# Optical_indication.net
KiCad netlist of a schematic drawn in Altium Designer
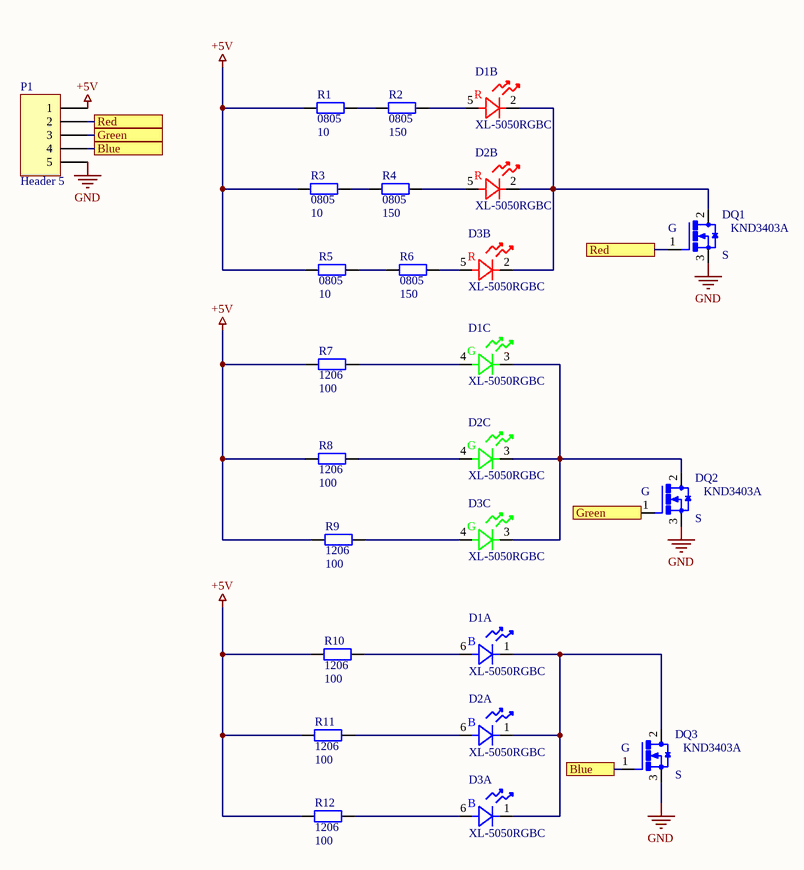
[diagram p0: Optical indication.SchDoc]

(export (version "E")
  (design (tool "Eeschema 10.0.6"))
  (components
    (comp (ref "D1")
      (value "XL-5050RGBC")
      (footprint "XL-5050RGBC")
      (libsource (lib "XL-5050RGBC") (part "XL-5050RGBC"))
    )
    (comp (ref "D2")
      (value "XL-5050RGBC")
      (footprint "XL-5050RGBC")
      (libsource (lib "XL-5050RGBC") (part "XL-5050RGBC"))
    )
    (comp (ref "D3")
      (value "XL-5050RGBC")
      (footprint "XL-5050RGBC")
      (libsource (lib "XL-5050RGBC") (part "XL-5050RGBC"))
    )
    (comp (ref "P1")
      (value "Header 5")
      (footprint "HDR1X5")
      (description "Header, 5-Pin")
      (fields (field (name "PUBLISHER") "Altium Limited"))
      (libsource (lib "Miscellaneous Connectors") (part "Header 5"))
    )
    (comp (ref "Q1")
      (value "KND3403A")
      (footprint "TO252")
      (description "N-CHANNEL MOSFET")
      (libsource (lib "KND3403A") (part "KND3403A"))
    )
    (comp (ref "Q2")
      (value "KND3403A")
      (footprint "TO252")
      (description "N-CHANNEL MOSFET")
      (libsource (lib "KND3403A") (part "KND3403A"))
    )
    (comp (ref "Q3")
      (value "KND3403A")
      (footprint "TO252")
      (description "N-CHANNEL MOSFET")
      (libsource (lib "KND3403A") (part "KND3403A"))
    )
    (comp (ref "R1")
      (value "0805")
      (footprint "AXIAL-0.4")
      (description "Resistor")
      (fields (field (name "ALTIUM_VALUE") "10") (field (name "PUBLISHER") "Altium Limited"))
      (libsource (lib "Miscellaneous Devices") (part "Res2"))
    )
    (comp (ref "R2")
      (value "0805")
      (footprint "AXIAL-0.4")
      (description "Resistor")
      (fields (field (name "ALTIUM_VALUE") "150") (field (name "PUBLISHER") "Altium Limited"))
      (libsource (lib "") (part "Res2_1"))
    )
    (comp (ref "R3")
      (value "0805")
      (footprint "AXIAL-0.4")
      (description "Resistor")
      (fields (field (name "ALTIUM_VALUE") "10") (field (name "PUBLISHER") "Altium Limited"))
      (libsource (lib "Miscellaneous Devices") (part "Res2"))
    )
    (comp (ref "R4")
      (value "0805")
      (footprint "AXIAL-0.4")
      (description "Resistor")
      (fields (field (name "ALTIUM_VALUE") "150") (field (name "PUBLISHER") "Altium Limited"))
      (libsource (lib "") (part "Res2_1"))
    )
    (comp (ref "R5")
      (value "0805")
      (footprint "AXIAL-0.4")
      (description "Resistor")
      (fields (field (name "ALTIUM_VALUE") "10") (field (name "PUBLISHER") "Altium Limited"))
      (libsource (lib "Miscellaneous Devices") (part "Res2"))
    )
    (comp (ref "R6")
      (value "0805")
      (footprint "AXIAL-0.4")
      (description "Resistor")
      (fields (field (name "ALTIUM_VALUE") "150") (field (name "PUBLISHER") "Altium Limited"))
      (libsource (lib "Miscellaneous Devices") (part "Res2"))
    )
    (comp (ref "R7")
      (value "1206")
      (footprint "AXIAL-0.4")
      (description "Resistor")
      (fields (field (name "ALTIUM_VALUE") "100") (field (name "PUBLISHER") "Altium Limited"))
      (libsource (lib "Miscellaneous Devices") (part "Res2"))
    )
    (comp (ref "R8")
      (value "1206")
      (footprint "AXIAL-0.4")
      (description "Resistor")
      (fields (field (name "ALTIUM_VALUE") "100") (field (name "PUBLISHER") "Altium Limited"))
      (libsource (lib "Miscellaneous Devices") (part "Res2"))
    )
    (comp (ref "R9")
      (value "1206")
      (footprint "AXIAL-0.4")
      (description "Resistor")
      (fields (field (name "ALTIUM_VALUE") "100") (field (name "PUBLISHER") "Altium Limited"))
      (libsource (lib "Miscellaneous Devices") (part "Res2"))
    )
    (comp (ref "R10")
      (value "1206")
      (footprint "AXIAL-0.4")
      (description "Resistor")
      (fields (field (name "ALTIUM_VALUE") "100") (field (name "PUBLISHER") "Altium Limited"))
      (libsource (lib "Miscellaneous Devices") (part "Res2"))
    )
    (comp (ref "R11")
      (value "1206")
      (footprint "AXIAL-0.4")
      (description "Resistor")
      (fields (field (name "ALTIUM_VALUE") "100") (field (name "PUBLISHER") "Altium Limited"))
      (libsource (lib "Miscellaneous Devices") (part "Res2"))
    )
    (comp (ref "R12")
      (value "1206")
      (footprint "AXIAL-0.4")
      (description "Resistor")
      (fields (field (name "ALTIUM_VALUE") "100") (field (name "PUBLISHER") "Altium Limited"))
      (libsource (lib "Miscellaneous Devices") (part "Res2"))
    )
  )
  (nets
    (net (code "1") (name "+5V") (class "Default")
      (node (ref "P1") (pin "1") (pinfunction "1_1") (pintype "passive"))
      (node (ref "R1") (pin "2") (pinfunction "2_2") (pintype "passive"))
      (node (ref "R10") (pin "2") (pinfunction "2_2") (pintype "passive"))
      (node (ref "R11") (pin "2") (pinfunction "2_2") (pintype "passive"))
      (node (ref "R12") (pin "2") (pinfunction "2_2") (pintype "passive"))
      (node (ref "R3") (pin "2") (pinfunction "2_2") (pintype "passive"))
      (node (ref "R5") (pin "2") (pinfunction "2_2") (pintype "passive"))
      (node (ref "R7") (pin "2") (pinfunction "2_2") (pintype "passive"))
      (node (ref "R8") (pin "2") (pinfunction "2_2") (pintype "passive"))
      (node (ref "R9") (pin "2") (pinfunction "2_2") (pintype "passive"))
    )
    (net (code "2") (name "/Blue") (class "Default")
      (node (ref "P1") (pin "4") (pinfunction "4_4") (pintype "passive"))
      (node (ref "Q3") (pin "1") (pinfunction "G_1") (pintype "passive"))
    )
    (net (code "3") (name "/Green") (class "Default")
      (node (ref "P1") (pin "3") (pinfunction "3_3") (pintype "passive"))
      (node (ref "Q2") (pin "1") (pinfunction "G_1") (pintype "passive"))
    )
    (net (code "4") (name "/Red") (class "Default")
      (node (ref "P1") (pin "2") (pinfunction "2_2") (pintype "passive"))
      (node (ref "Q1") (pin "1") (pinfunction "G_1") (pintype "passive"))
    )
    (net (code "5") (name "GND") (class "Default")
      (node (ref "P1") (pin "5") (pinfunction "5_5") (pintype "passive"))
      (node (ref "Q1") (pin "3") (pinfunction "S_3") (pintype "passive"))
      (node (ref "Q2") (pin "3") (pinfunction "S_3") (pintype "passive"))
      (node (ref "Q3") (pin "3") (pinfunction "S_3") (pintype "passive"))
    )
    (net (code "6") (name "Net-(D1-Pad4)") (class "Default")
      (node (ref "D1") (pin "4") (pintype "passive"))
      (node (ref "R7") (pin "1") (pinfunction "1_1") (pintype "passive"))
    )
    (net (code "7") (name "Net-(D1-Pad5)") (class "Default")
      (node (ref "D1") (pin "5") (pintype "passive"))
      (node (ref "R2") (pin "2") (pinfunction "2_2") (pintype "passive"))
    )
    (net (code "8") (name "Net-(D1-Pad6)") (class "Default")
      (node (ref "D1") (pin "6") (pinfunction "6_6") (pintype "passive"))
      (node (ref "R10") (pin "1") (pinfunction "1_1") (pintype "passive"))
    )
    (net (code "9") (name "Net-(D2-Pad4)") (class "Default")
      (node (ref "D2") (pin "4") (pintype "passive"))
      (node (ref "R8") (pin "1") (pinfunction "1_1") (pintype "passive"))
    )
    (net (code "10") (name "Net-(D2-Pad5)") (class "Default")
      (node (ref "D2") (pin "5") (pintype "passive"))
      (node (ref "R4") (pin "2") (pinfunction "2_2") (pintype "passive"))
    )
    (net (code "11") (name "Net-(D2-Pad6)") (class "Default")
      (node (ref "D2") (pin "6") (pinfunction "6_6") (pintype "passive"))
      (node (ref "R11") (pin "1") (pinfunction "1_1") (pintype "passive"))
    )
    (net (code "12") (name "Net-(D3-Pad4)") (class "Default")
      (node (ref "D3") (pin "4") (pintype "passive"))
      (node (ref "R9") (pin "1") (pinfunction "1_1") (pintype "passive"))
    )
    (net (code "13") (name "Net-(D3-Pad5)") (class "Default")
      (node (ref "D3") (pin "5") (pintype "passive"))
      (node (ref "R6") (pin "1") (pinfunction "1_1") (pintype "passive"))
    )
    (net (code "14") (name "Net-(D3-Pad6)") (class "Default")
      (node (ref "D3") (pin "6") (pinfunction "6_6") (pintype "passive"))
      (node (ref "R12") (pin "1") (pinfunction "1_1") (pintype "passive"))
    )
    (net (code "15") (name "Net-(Q1-D)") (class "Default")
      (node (ref "D1") (pin "2") (pinfunction "2_2") (pintype "passive"))
      (node (ref "D2") (pin "2") (pinfunction "2_2") (pintype "passive"))
      (node (ref "D3") (pin "2") (pinfunction "2_2") (pintype "passive"))
      (node (ref "Q1") (pin "2") (pinfunction "D_2") (pintype "passive"))
    )
    (net (code "16") (name "Net-(Q2-D)") (class "Default")
      (node (ref "D1") (pin "3") (pintype "passive"))
      (node (ref "D2") (pin "3") (pintype "passive"))
      (node (ref "D3") (pin "3") (pintype "passive"))
      (node (ref "Q2") (pin "2") (pinfunction "D_2") (pintype "passive"))
    )
    (net (code "17") (name "Net-(Q3-D)") (class "Default")
      (node (ref "D1") (pin "1") (pinfunction "1_1") (pintype "passive"))
      (node (ref "D2") (pin "1") (pinfunction "1_1") (pintype "passive"))
      (node (ref "D3") (pin "1") (pinfunction "1_1") (pintype "passive"))
      (node (ref "Q3") (pin "2") (pinfunction "D_2") (pintype "passive"))
    )
    (net (code "18") (name "Net-(R1-Pad1)") (class "Default")
      (node (ref "R1") (pin "1") (pinfunction "1_1") (pintype "passive"))
      (node (ref "R2") (pin "1") (pinfunction "1_1") (pintype "passive"))
    )
    (net (code "19") (name "Net-(R3-Pad1)") (class "Default")
      (node (ref "R3") (pin "1") (pinfunction "1_1") (pintype "passive"))
      (node (ref "R4") (pin "1") (pinfunction "1_1") (pintype "passive"))
    )
    (net (code "20") (name "Net-(R5-Pad1)") (class "Default")
      (node (ref "R5") (pin "1") (pinfunction "1_1") (pintype "passive"))
      (node (ref "R6") (pin "2") (pinfunction "2_2") (pintype "passive"))
    )
  )
)
